# Feather-Extension.net
KiCad netlist of a schematic drawn in EAGLE
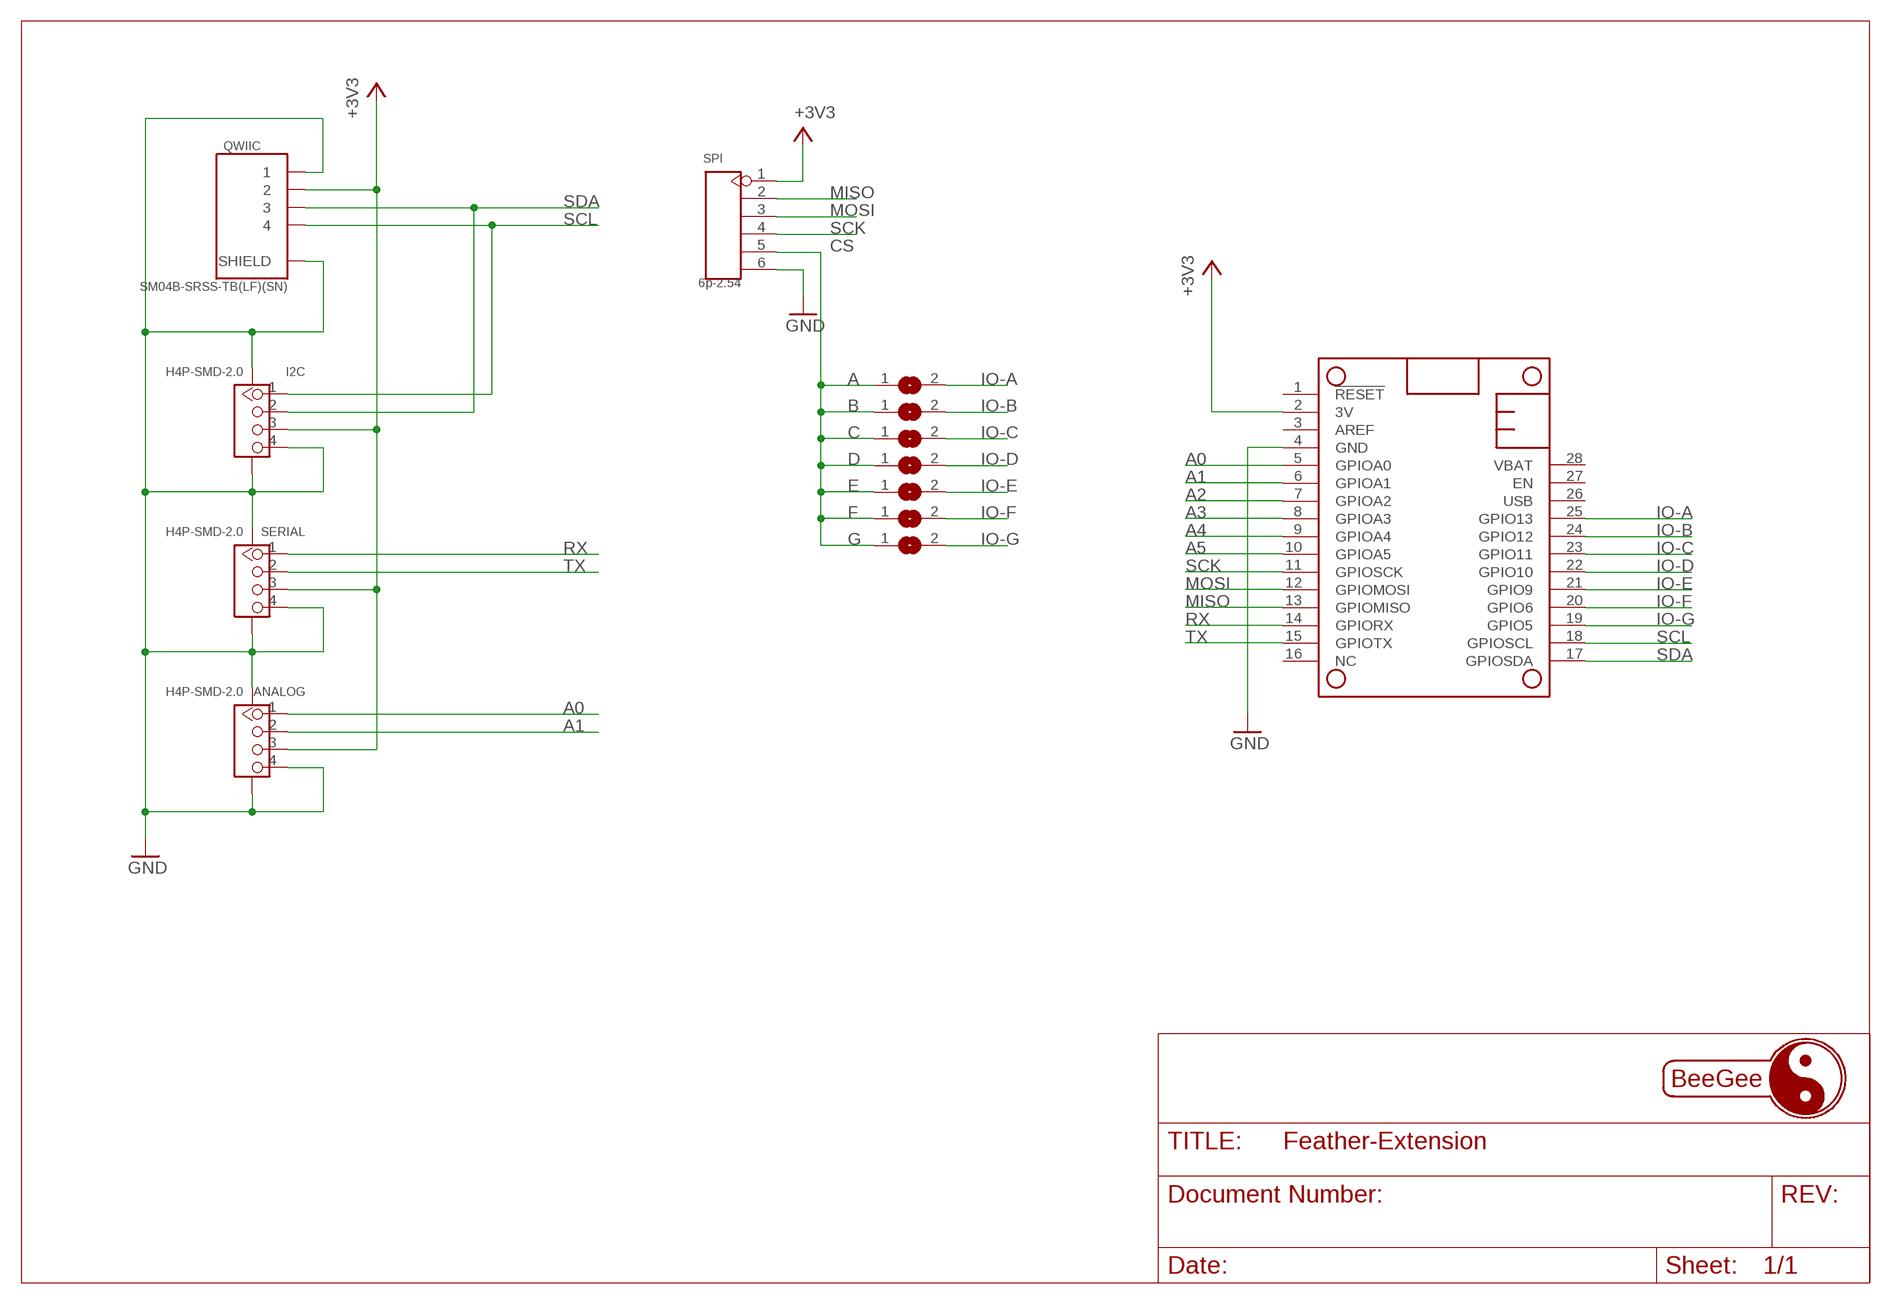
[diagram p0: schematic, sheet 1]

(export (version "E")
  (design (tool "Eeschema 10.0.6"))
  (components
    (comp (ref "A") (value "SJ") (footprint "eagle-import:SJ") (libsource (lib "eagle-import") (part "SJ")))
    (comp (ref "ANALOG")
      (value "H4P-SMD-2.0")
      (footprint "eagle-import:HW4-SMD-2.0")
      (libsource (lib "eagle-import") (part "GROVE-CONNECTOR-SMD(4+2P-2.0)"))
    )
    (comp (ref "B") (value "SJ") (footprint "eagle-import:SJ") (libsource (lib "eagle-import") (part "SJ")))
    (comp (ref "C") (value "SJ") (footprint "eagle-import:SJ") (libsource (lib "eagle-import") (part "SJ")))
    (comp (ref "D") (value "SJ") (footprint "eagle-import:SJ") (libsource (lib "eagle-import") (part "SJ")))
    (comp (ref "E") (value "SJ") (footprint "eagle-import:SJ") (libsource (lib "eagle-import") (part "SJ")))
    (comp (ref "F") (value "SJ") (footprint "eagle-import:SJ") (libsource (lib "eagle-import") (part "SJ")))
    (comp (ref "G") (value "SJ") (footprint "eagle-import:SJ") (libsource (lib "eagle-import") (part "SJ")))
    (comp (ref "I2C")
      (value "H4P-SMD-2.0")
      (footprint "eagle-import:HW4-SMD-2.0")
      (libsource (lib "eagle-import") (part "GROVE-CONNECTOR-SMD(4+2P-2.0)"))
    )
    (comp (ref "MS2")
      (value "FEATHERWING")
      (footprint "eagle-import:FEATHERWING")
      (libsource (lib "eagle-import") (part "FEATHERWING"))
    )
    (comp (ref "QWIIC")
      (value "SM04B-SRSS-TB(LF)(SN)")
      (footprint "eagle-import:JST_SM04B-SRSS-TB(LF)(SN)")
      (fields (field (name "MF") "JST Sales") (field (name "MP") "SM04B-SRSS-TB_LF__SN_"))
      (libsource (lib "eagle-import") (part "SM04B-SRSS-TB(LF)(SN)"))
    )
    (comp (ref "SERIAL")
      (value "H4P-SMD-2.0")
      (footprint "eagle-import:HW4-SMD-2.0")
      (libsource (lib "eagle-import") (part "GROVE-CONNECTOR-SMD(4+2P-2.0)"))
    )
    (comp (ref "SPI")
      (value "6p-2.54")
      (footprint "eagle-import:H6-2.54")
      (fields (field (name "MPN") "P125-1106A1BS116A1"))
      (libsource (lib "eagle-import") (part "DIP-BLACK-MALE-HEADER(6P-2.54)"))
    )
  )
  (nets
    (net (code "1") (name "+3V3") (class "Default")
      (node (ref "ANALOG") (pin "3") (pinfunction "3_3") (pintype "bidirectional"))
      (node (ref "I2C") (pin "3") (pinfunction "3_3") (pintype "bidirectional"))
      (node (ref "MS2") (pin "2") (pinfunction "3V_2") (pintype "power_in"))
      (node (ref "QWIIC") (pin "2") (pinfunction "2_2") (pintype "passive"))
      (node (ref "SERIAL") (pin "3") (pinfunction "3_3") (pintype "bidirectional"))
      (node (ref "SPI") (pin "1") (pinfunction "1_1") (pintype "bidirectional"))
    )
    (net (code "2") (name "/A0") (class "Default")
      (node (ref "ANALOG") (pin "1") (pinfunction "1_1") (pintype "bidirectional"))
      (node (ref "MS2") (pin "5") (pinfunction "GPIOA0_5") (pintype "bidirectional"))
    )
    (net (code "3") (name "/A1") (class "Default")
      (node (ref "ANALOG") (pin "2") (pinfunction "2_2") (pintype "bidirectional"))
      (node (ref "MS2") (pin "6") (pinfunction "GPIOA1_6") (pintype "bidirectional"))
    )
    (net (code "4") (name "/A2") (class "Default")
      (node (ref "MS2") (pin "7") (pinfunction "GPIOA2_7") (pintype "bidirectional"))
    )
    (net (code "5") (name "/A3") (class "Default")
      (node (ref "MS2") (pin "8") (pinfunction "GPIOA3_8") (pintype "bidirectional"))
    )
    (net (code "6") (name "/A4") (class "Default")
      (node (ref "MS2") (pin "9") (pinfunction "GPIOA4_9") (pintype "bidirectional"))
    )
    (net (code "7") (name "/A5") (class "Default")
      (node (ref "MS2") (pin "10") (pinfunction "GPIOA5_10") (pintype "bidirectional"))
    )
    (net (code "8") (name "/CS") (class "Default")
      (node (ref "A") (pin "1") (pinfunction "1_1") (pintype "passive"))
      (node (ref "B") (pin "1") (pinfunction "1_1") (pintype "passive"))
      (node (ref "C") (pin "1") (pinfunction "1_1") (pintype "passive"))
      (node (ref "D") (pin "1") (pinfunction "1_1") (pintype "passive"))
      (node (ref "E") (pin "1") (pinfunction "1_1") (pintype "passive"))
      (node (ref "F") (pin "1") (pinfunction "1_1") (pintype "passive"))
      (node (ref "G") (pin "1") (pinfunction "1_1") (pintype "passive"))
      (node (ref "SPI") (pin "5") (pinfunction "5_5") (pintype "bidirectional"))
    )
    (net (code "9") (name "/IO-A") (class "Default")
      (node (ref "A") (pin "2") (pinfunction "2_2") (pintype "passive"))
      (node (ref "MS2") (pin "25") (pinfunction "GPIO13_25") (pintype "bidirectional"))
    )
    (net (code "10") (name "/IO-B") (class "Default")
      (node (ref "B") (pin "2") (pinfunction "2_2") (pintype "passive"))
      (node (ref "MS2") (pin "24") (pinfunction "GPIO12_24") (pintype "bidirectional"))
    )
    (net (code "11") (name "/IO-C") (class "Default")
      (node (ref "C") (pin "2") (pinfunction "2_2") (pintype "passive"))
      (node (ref "MS2") (pin "23") (pinfunction "GPIO11_23") (pintype "bidirectional"))
    )
    (net (code "12") (name "/IO-D") (class "Default")
      (node (ref "D") (pin "2") (pinfunction "2_2") (pintype "passive"))
      (node (ref "MS2") (pin "22") (pinfunction "GPIO10_22") (pintype "bidirectional"))
    )
    (net (code "13") (name "/IO-E") (class "Default")
      (node (ref "E") (pin "2") (pinfunction "2_2") (pintype "passive"))
      (node (ref "MS2") (pin "21") (pinfunction "GPIO9_21") (pintype "bidirectional"))
    )
    (net (code "14") (name "/IO-F") (class "Default")
      (node (ref "F") (pin "2") (pinfunction "2_2") (pintype "passive"))
      (node (ref "MS2") (pin "20") (pinfunction "GPIO6_20") (pintype "bidirectional"))
    )
    (net (code "15") (name "/IO-G") (class "Default")
      (node (ref "G") (pin "2") (pinfunction "2_2") (pintype "passive"))
      (node (ref "MS2") (pin "19") (pinfunction "GPIO5_19") (pintype "bidirectional"))
    )
    (net (code "16") (name "/MISO") (class "Default")
      (node (ref "MS2") (pin "13") (pinfunction "GPIOMISO_13") (pintype "bidirectional"))
      (node (ref "SPI") (pin "2") (pinfunction "2_2") (pintype "bidirectional"))
    )
    (net (code "17") (name "/MOSI") (class "Default")
      (node (ref "MS2") (pin "12") (pinfunction "GPIOMOSI_12") (pintype "bidirectional"))
      (node (ref "SPI") (pin "3") (pinfunction "3_3") (pintype "bidirectional"))
    )
    (net (code "18") (name "/RX") (class "Default")
      (node (ref "MS2") (pin "14") (pinfunction "GPIORX_14") (pintype "bidirectional"))
      (node (ref "SERIAL") (pin "1") (pinfunction "1_1") (pintype "bidirectional"))
    )
    (net (code "19") (name "/SCK") (class "Default")
      (node (ref "MS2") (pin "11") (pinfunction "GPIOSCK_11") (pintype "bidirectional"))
      (node (ref "SPI") (pin "4") (pinfunction "4_4") (pintype "bidirectional"))
    )
    (net (code "20") (name "/SCL") (class "Default")
      (node (ref "I2C") (pin "1") (pinfunction "1_1") (pintype "bidirectional"))
      (node (ref "MS2") (pin "18") (pinfunction "GPIOSCL_18") (pintype "bidirectional"))
      (node (ref "QWIIC") (pin "4") (pinfunction "4_4") (pintype "passive"))
    )
    (net (code "21") (name "/SDA") (class "Default")
      (node (ref "I2C") (pin "2") (pinfunction "2_2") (pintype "bidirectional"))
      (node (ref "MS2") (pin "17") (pinfunction "GPIOSDA_17") (pintype "bidirectional"))
      (node (ref "QWIIC") (pin "3") (pinfunction "3_3") (pintype "passive"))
    )
    (net (code "22") (name "/TX") (class "Default")
      (node (ref "MS2") (pin "15") (pinfunction "GPIOTX_15") (pintype "bidirectional"))
      (node (ref "SERIAL") (pin "2") (pinfunction "2_2") (pintype "bidirectional"))
    )
    (net (code "23") (name "/USB") (class "Default")
      (node (ref "MS2") (pin "26") (pinfunction "USB_26") (pintype "power_in"))
    )
    (net (code "24") (name "/VBAT") (class "Default")
      (node (ref "MS2") (pin "28") (pinfunction "VBAT_28") (pintype "power_in"))
    )
    (net (code "25") (name "GND") (class "Default")
      (node (ref "ANALOG") (pin "4") (pinfunction "4_4") (pintype "bidirectional"))
      (node (ref "ANALOG") (pin "SS1") (pinfunction "SS1_SS1") (pintype "bidirectional"))
      (node (ref "ANALOG") (pin "SS2") (pinfunction "SS2_SS2") (pintype "bidirectional"))
      (node (ref "I2C") (pin "4") (pinfunction "4_4") (pintype "bidirectional"))
      (node (ref "I2C") (pin "SS1") (pinfunction "SS1_SS1") (pintype "bidirectional"))
      (node (ref "I2C") (pin "SS2") (pinfunction "SS2_SS2") (pintype "bidirectional"))
      (node (ref "MS2") (pin "4") (pinfunction "GND_4") (pintype "power_in"))
      (node (ref "QWIIC") (pin "1") (pinfunction "1_1") (pintype "passive"))
      (node (ref "QWIIC") (pin "S1") (pinfunction "SHIELD_S1") (pintype "passive"))
      (node (ref "QWIIC") (pin "S2") (pinfunction "SHIELD_S2") (pintype "passive"))
      (node (ref "SERIAL") (pin "4") (pinfunction "4_4") (pintype "bidirectional"))
      (node (ref "SERIAL") (pin "SS1") (pinfunction "SS1_SS1") (pintype "bidirectional"))
      (node (ref "SERIAL") (pin "SS2") (pinfunction "SS2_SS2") (pintype "bidirectional"))
      (node (ref "SPI") (pin "6") (pinfunction "6_6") (pintype "bidirectional"))
    )
    (net (code "26") (name "unconnected-(MS2-AREF-Pad3)") (class "Default")
      (node (ref "MS2") (pin "3") (pinfunction "AREF_3") (pintype "passive"))
    )
    (net (code "27") (name "unconnected-(MS2-EN-Pad27)") (class "Default")
      (node (ref "MS2") (pin "27") (pinfunction "EN_27") (pintype "passive"))
    )
    (net (code "28") (name "unconnected-(MS2-NC-Pad16)") (class "Default")
      (node (ref "MS2") (pin "16") (pinfunction "NC_16") (pintype "passive"))
    )
    (net (code "29") (name "unconnected-(MS2-~{RESET}-Pad1)") (class "Default")
      (node (ref "MS2") (pin "1") (pinfunction "~{RESET}_1") (pintype "input"))
    )
  )
)
